# power.net
KiCad netlist of a schematic drawn in Altium Designer
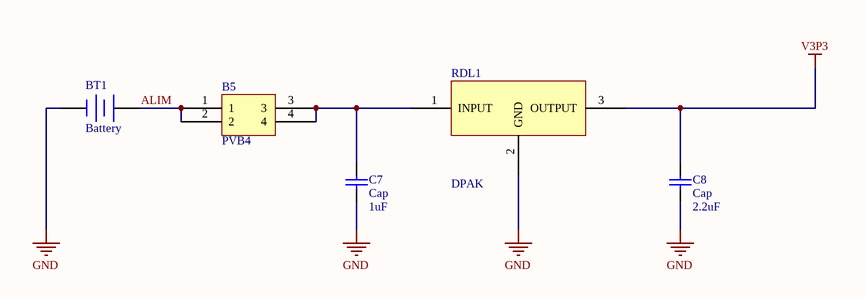
[diagram p0: power.SchDoc]

(export (version "E")
  (design (tool "Eeschema 10.0.6"))
  (components
    (comp (ref "B5")
      (value "PVB4")
      (footprint "BUTTON ON/OFF")
      (description "Push switch ON/OFF")
      (libsource (lib "libProject") (part "BUTTON_ON"))
    )
    (comp (ref "BT1")
      (value "Battery")
      (footprint "SUP_PILE")
      (description "One-cell Battery AA")
      (fields (field (name "PUBLISHER") "Altium Limited"))
      (libsource (lib "Miscellaneous Devices") (part "Battery"))
    )
    (comp (ref "C7")
      (value "Cap")
      (footprint "Capacitor")
      (description "Capacitor")
      (fields (field (name "ALTIUM_VALUE") "1uF") (field (name "PUBLISHER") "Altium Limited"))
      (libsource (lib "Miscellaneous Devices") (part "Cap"))
    )
    (comp (ref "C8")
      (value "Cap")
      (footprint "Capacitor")
      (description "Capacitor")
      (fields (field (name "ALTIUM_VALUE") "2.2uF") (field (name "PUBLISHER") "Altium Limited"))
      (libsource (lib "Miscellaneous Devices") (part "Cap"))
    )
    (comp (ref "RDL1") (value "DPAK") (footprint "REG_DEC_LIN") (libsource (lib "libProject") (part "DPAK")))
  )
  (nets
    (net (code "1") (name "/ALIM") (class "Default")
      (node (ref "B5") (pin "1") (pinfunction "1_1") (pintype "passive"))
      (node (ref "B5") (pin "2") (pinfunction "2_2") (pintype "passive"))
      (node (ref "BT1") (pin "1") (pinfunction "+_1") (pintype "power_in"))
    )
    (net (code "2") (name "GND") (class "Default")
      (node (ref "BT1") (pin "2") (pinfunction "-_2") (pintype "power_in"))
      (node (ref "C7") (pin "1") (pinfunction "1_1") (pintype "passive"))
      (node (ref "C8") (pin "1") (pinfunction "1_1") (pintype "passive"))
      (node (ref "RDL1") (pin "2") (pinfunction "GND_2") (pintype "power_in"))
    )
    (net (code "3") (name "Net-(RDL1-INPUT)") (class "Default")
      (node (ref "B5") (pin "3") (pinfunction "3_3") (pintype "passive"))
      (node (ref "B5") (pin "4") (pinfunction "4_4") (pintype "passive"))
      (node (ref "C7") (pin "2") (pinfunction "2_2") (pintype "passive"))
      (node (ref "RDL1") (pin "1") (pinfunction "INPUT_1") (pintype "power_in"))
    )
    (net (code "4") (name "V3P3") (class "Default")
      (node (ref "C8") (pin "2") (pinfunction "2_2") (pintype "passive"))
      (node (ref "RDL1") (pin "3") (pinfunction "OUTPUT_3") (pintype "power_in"))
    )
  )
)
